# MB1296-STLINK.net
KiCad netlist of a schematic drawn in Altium Designer
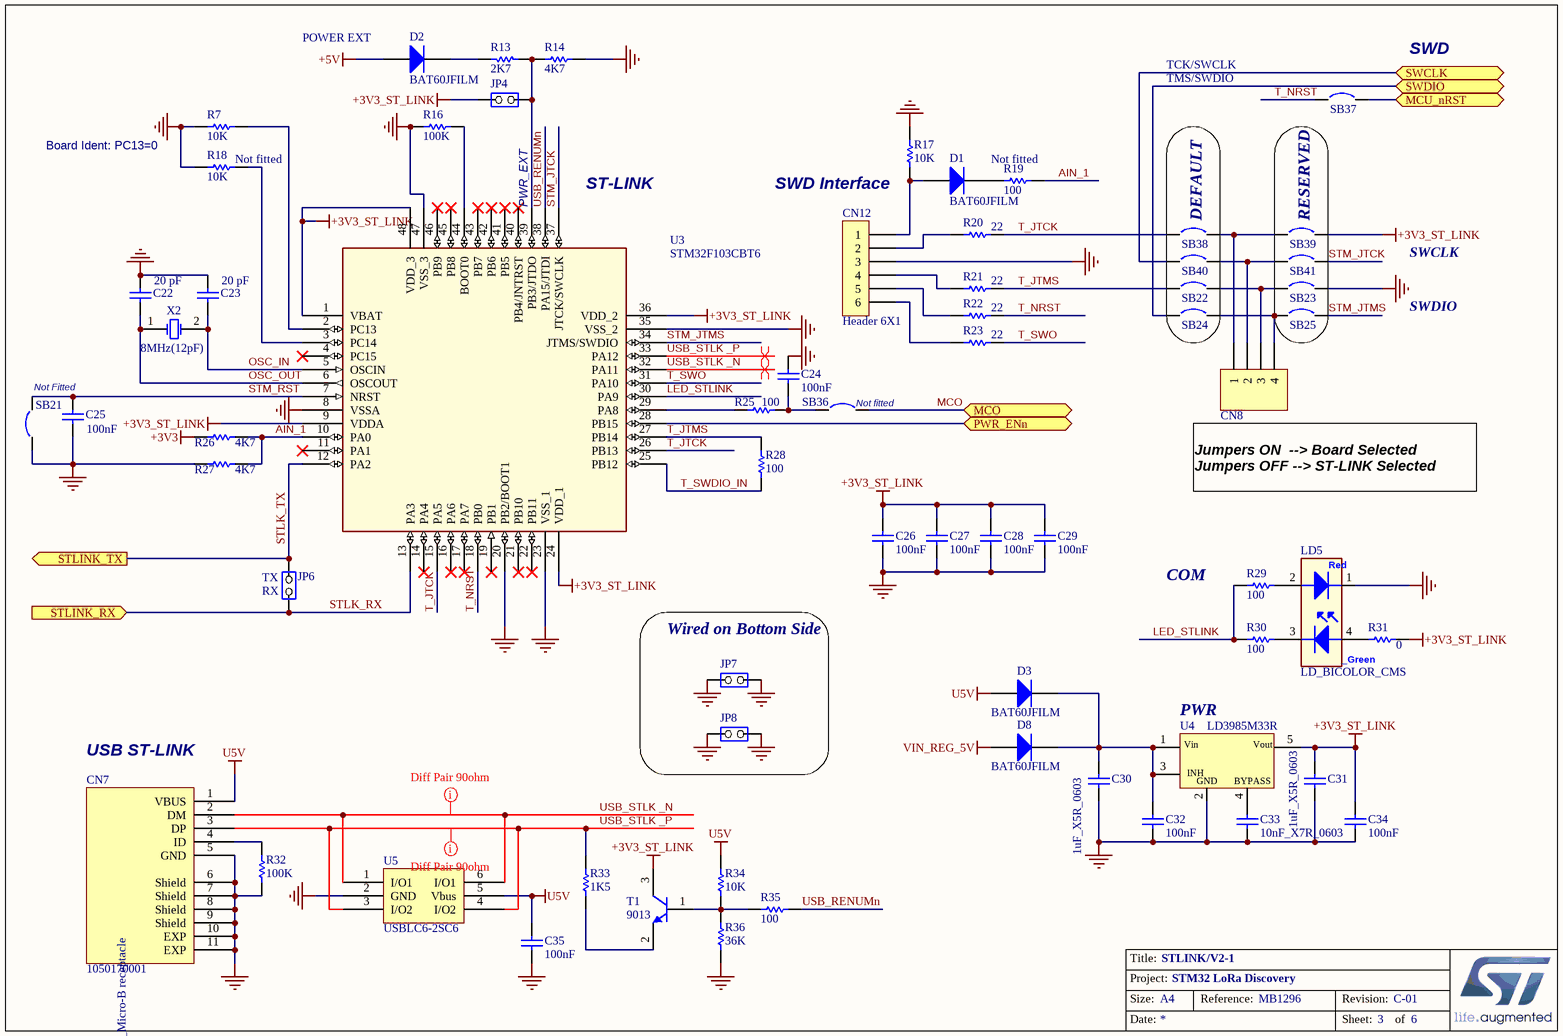
[diagram p0: MB1296-STLINK.SchDoc]

(export (version "E")
  (design (tool "Eeschema 10.0.6"))
  (components
    (comp (ref "C22")
      (value "20 pF")
      (footprint "0603C")
      (description "Capacitor 0603")
      (fields (field (name "MANUFACTURER") "YAGEO") (field (name "PROVIDED BY") "Subcon"))
      (libsource (lib "MCD16-033-STM32_LRA_Eval_Board_1") (part "Capacitor_ST"))
    )
    (comp (ref "C23")
      (value "20 pF")
      (footprint "0603C")
      (description "Capacitor 0603")
      (fields (field (name "MANUFACTURER") "YAGEO") (field (name "PROVIDED BY") "Subcon"))
      (libsource (lib "MCD16-033-STM32_LRA_Eval_Board_1") (part "Capacitor_ST"))
    )
    (comp (ref "C24")
      (value "100nF")
      (footprint "0603C")
      (description "Capacitor 100nF")
      (fields (field (name "MANUFACTURER") "YAGEO") (field (name "PROVIDED BY") "Subcon"))
      (libsource (lib "MCD16-033-STM32_LRA_Eval_Board_1") (part "CAP"))
    )
    (comp (ref "C25")
      (value "100nF")
      (footprint "0603C")
      (description "Capacitor 100nF")
      (fields (field (name "MANUFACTURER") "YAGEO") (field (name "PROVIDED BY") "Subcon"))
      (libsource (lib "MCD16-033-STM32_LRA_Eval_Board_1") (part "CAP"))
    )
    (comp (ref "C26")
      (value "100nF")
      (footprint "0603C")
      (description "Capacitor 100nF")
      (fields (field (name "MANUFACTURER") "YAGEO") (field (name "PROVIDED BY") "Subcon"))
      (libsource (lib "MCD16-033-STM32_LRA_Eval_Board_1") (part "CAP"))
    )
    (comp (ref "C27")
      (value "100nF")
      (footprint "0603C")
      (description "Capacitor 100nF")
      (fields (field (name "MANUFACTURER") "YAGEO") (field (name "PROVIDED BY") "Subcon"))
      (libsource (lib "MCD16-033-STM32_LRA_Eval_Board_1") (part "CAP"))
    )
    (comp (ref "C28")
      (value "100nF")
      (footprint "0603C")
      (description "Capacitor 100nF")
      (fields (field (name "MANUFACTURER") "YAGEO") (field (name "PROVIDED BY") "Subcon"))
      (libsource (lib "MCD16-033-STM32_LRA_Eval_Board_1") (part "CAP"))
    )
    (comp (ref "C29")
      (value "100nF")
      (footprint "0603C")
      (description "Capacitor 100nF")
      (fields (field (name "MANUFACTURER") "YAGEO") (field (name "PROVIDED BY") "Subcon"))
      (libsource (lib "MCD16-033-STM32_LRA_Eval_Board_1") (part "CAP"))
    )
    (comp (ref "C30")
      (value "1uF_X5R_0603")
      (footprint "0603C")
      (description "0603  X5R 1µF")
      (fields (field (name "MANUFACTURER") "YAGEO") (field (name "PROVIDED BY") "Subcon"))
      (libsource (lib "MCD16-033-STM32_LRA_Eval_Board_1") (part "CAP SMD 0603  X5R 1µF 25V 10%"))
    )
    (comp (ref "C31")
      (value "1uF_X5R_0603")
      (footprint "0603C")
      (description "0603  X5R 1µF")
      (fields (field (name "MANUFACTURER") "YAGEO") (field (name "PROVIDED BY") "Subcon"))
      (libsource (lib "MCD16-033-STM32_LRA_Eval_Board_1") (part "CAP SMD 0603  X5R 1µF 25V 10%"))
    )
    (comp (ref "C32")
      (value "100nF")
      (footprint "0603C")
      (description "Capacitor 100nF")
      (fields (field (name "MANUFACTURER") "YAGEO") (field (name "PROVIDED BY") "Subcon"))
      (libsource (lib "MCD16-033-STM32_LRA_Eval_Board_1") (part "CAP"))
    )
    (comp (ref "C33")
      (value "10nF_X7R_0603")
      (footprint "0603C")
      (description "0603  X7R 10NF")
      (fields (field (name "MANUFACTURER") "YAGEO") (field (name "PROVIDED BY") "Subcon"))
      (libsource (lib "MCD16-033-STM32_LRA_Eval_Board_1") (part "CAP SMD 0603  X7R 10000PF 50V 10%"))
    )
    (comp (ref "C34")
      (value "100nF")
      (footprint "0603C")
      (description "Capacitor 100nF")
      (fields (field (name "MANUFACTURER") "YAGEO") (field (name "PROVIDED BY") "Subcon"))
      (libsource (lib "MCD16-033-STM32_LRA_Eval_Board_1") (part "CAP"))
    )
    (comp (ref "C35")
      (value "100nF")
      (footprint "0603C")
      (description "Capacitor 100nF")
      (fields (field (name "MANUFACTURER") "YAGEO") (field (name "PROVIDED BY") "Subcon"))
      (libsource (lib "MCD16-033-STM32_LRA_Eval_Board_1") (part "CAP"))
    )
    (comp (ref "CN7")
      (value "1050170001")
      (footprint "Molex_1050170001")
      (libsource (lib "Smartphone_accessory") (part "1050170001"))
    )
    (comp (ref "CN8")
      (value "Header 4")
      (footprint "SIP4")
      (description "Header, 4-Pin, Single row")
      (fields (field (name "MANUFACTURER") "Lyconn") (field (name "PROVIDED BY") "Subcon"))
      (libsource (lib "MCD16-033-STM32_LRA_Eval_Board_1") (part "Header 4"))
    )
    (comp (ref "CN12")
      (value "Header 6X1")
      (footprint "Header 1x6 Female (Wrapping)")
      (description "Header, 6-Pin, Single row")
      (fields (field (name "MANUFACTURER") "Lyconn") (field (name "PROVIDED BY") "Subcon"))
      (libsource (lib "MCD16-033-STM32_LRA_Eval_Board_1") (part "Header 6X1"))
    )
    (comp (ref "D1")
      (value "BAT60JFILM")
      (footprint "SOD323/A")
      (fields (field (name "MANUFACTURER") "STM"))
      (libsource (lib "MCD16-033-STM32_LRA_Eval_Board_1") (part "BAT60JFILM"))
    )
    (comp (ref "D2")
      (value "BAT60JFILM")
      (footprint "SOD323/A")
      (fields (field (name "MANUFACTURER") "STM"))
      (libsource (lib "MCD16-033-STM32_LRA_Eval_Board_1") (part "BAT60JFILM"))
    )
    (comp (ref "D3")
      (value "BAT60JFILM")
      (footprint "SOD323/A")
      (fields (field (name "MANUFACTURER") "STM"))
      (libsource (lib "MCD16-033-STM32_LRA_Eval_Board_1") (part "BAT60JFILM"))
    )
    (comp (ref "D8")
      (value "BAT60JFILM")
      (footprint "SOD323/A")
      (fields (field (name "MANUFACTURER") "STM"))
      (libsource (lib "MCD16-033-STM32_LRA_Eval_Board_1") (part "BAT60JFILM"))
    )
    (comp (ref "JP4")
      (value "~")
      (footprint "SIP2/2.54")
      (fields (field (name "MANUFACTURER") "Lyconn") (field (name "PROVIDED BY") "Subcon"))
      (libsource (lib "MCD16-033-STM32_LRA_Eval_Board_1") (part "JP2"))
    )
    (comp (ref "JP6")
      (value "~")
      (footprint "SIP2/2.54")
      (fields (field (name "MANUFACTURER") "Lyconn") (field (name "PROVIDED BY") "Subcon"))
      (libsource (lib "MCD16-033-STM32_LRA_Eval_Board_1") (part "JP2"))
    )
    (comp (ref "JP7")
      (value "~")
      (footprint "SIP2/2.54-BOT")
      (fields (field (name "MANUFACTURER") "Lyconn") (field (name "PROVIDED BY") "Subcon"))
      (libsource (lib "MCD16-033-STM32_LRA_Eval_Board_1") (part "JP2"))
    )
    (comp (ref "JP8")
      (value "~")
      (footprint "SIP2/2.54-BOT")
      (fields (field (name "MANUFACTURER") "Lyconn") (field (name "PROVIDED BY") "Subcon"))
      (libsource (lib "MCD16-033-STM32_LRA_Eval_Board_1") (part "JP2"))
    )
    (comp (ref "LD5")
      (value "LD_BICOLOR_CMS")
      (footprint "LED SMD HSMF-A201-A00J1")
      (description "Bicolor Led")
      (fields (field (name "MANUFACTURER") "everluck-led") (field (name "PROVIDED BY") "Subcon"))
      (libsource (lib "MCD16-033-STM32_LRA_Eval_Board_1") (part "LD_BICOLOR_CMS"))
    )
    (comp (ref "R7")
      (value "10K")
      (footprint "0603")
      (description "Resistor 0603")
      (fields (field (name "MANUFACTURER") "YAGEO") (field (name "PROVIDED BY") "Subcon"))
      (libsource (lib "MCD16-033-STM32_LRA_Eval_Board_1") (part "Resistor_ST"))
    )
    (comp (ref "R13")
      (value "2K7")
      (description "Resistor")
      (fields (field (name "PUBLISHER") "Altium Limited"))
      (libsource (lib "") (part "Res1_2"))
    )
    (comp (ref "R14")
      (value "4K7")
      (description "Resistor")
      (fields (field (name "MANUFACTURER") "YAGEO") (field (name "PROVIDED BY") "Subcon"))
      (libsource (lib "MCD16-033-STM32_LRA_Eval_Board_1") (part "res1_4"))
    )
    (comp (ref "R16")
      (value "100K")
      (footprint "0603")
      (description "0603 100K 75V 5% 0.1W")
      (fields (field (name "MANUFACTURER") "YAGEO") (field (name "PROVIDED BY") "Subcon"))
      (libsource (lib "MCD16-033-STM32_LRA_Eval_Board_1") (part "RES SMD 0603 100K 75V 5% 0.1W"))
    )
    (comp (ref "R17")
      (value "10K")
      (footprint "0603")
      (description "Resistor 0603")
      (fields (field (name "MANUFACTURER") "YAGEO") (field (name "PROVIDED BY") "Subcon"))
      (libsource (lib "MCD16-033-STM32_LRA_Eval_Board_1") (part "Resistor_ST"))
    )
    (comp (ref "R18")
      (value "10K")
      (footprint "0603")
      (description "Resistor 0603")
      (fields (field (name "MANUFACTURER") "YAGEO") (field (name "PROVIDED BY") "Subcon"))
      (libsource (lib "MCD16-033-STM32_LRA_Eval_Board_1") (part "Resistor_ST"))
    )
    (comp (ref "R19")
      (value "100")
      (footprint "0603")
      (description "Resistor 0603")
      (fields (field (name "MANUFACTURER") "YAGEO") (field (name "PROVIDED BY") "Subcon"))
      (libsource (lib "MCD16-033-STM32_LRA_Eval_Board_1") (part "Res1_1"))
    )
    (comp (ref "R20")
      (value "22")
      (footprint "0603")
      (description "Resistor 0603")
      (fields (field (name "MANUFACTURER") "YAGEO") (field (name "PROVIDED BY") "Subcon"))
      (libsource (lib "MCD16-033-STM32_LRA_Eval_Board_1") (part "Res1_1"))
    )
    (comp (ref "R21")
      (value "22")
      (footprint "0603")
      (description "Resistor 0603")
      (fields (field (name "MANUFACTURER") "YAGEO") (field (name "PROVIDED BY") "Subcon"))
      (libsource (lib "MCD16-033-STM32_LRA_Eval_Board_1") (part "Res1_1"))
    )
    (comp (ref "R22")
      (value "22")
      (footprint "0603")
      (description "Resistor 0603")
      (fields (field (name "MANUFACTURER") "YAGEO") (field (name "PROVIDED BY") "Subcon"))
      (libsource (lib "MCD16-033-STM32_LRA_Eval_Board_1") (part "Res1_1"))
    )
    (comp (ref "R23")
      (value "22")
      (footprint "0603")
      (description "Resistor 0603")
      (fields (field (name "MANUFACTURER") "YAGEO") (field (name "PROVIDED BY") "Subcon"))
      (libsource (lib "MCD16-033-STM32_LRA_Eval_Board_1") (part "Res1_1"))
    )
    (comp (ref "R25")
      (value "100")
      (footprint "0603")
      (description "Resistor 0603")
      (fields (field (name "MANUFACTURER") "YAGEO") (field (name "PROVIDED BY") "Subcon"))
      (libsource (lib "MCD16-033-STM32_LRA_Eval_Board_1") (part "Res1_1"))
    )
    (comp (ref "R26")
      (value "4K7")
      (description "Resistor")
      (fields (field (name "MANUFACTURER") "YAGEO") (field (name "PROVIDED BY") "Subcon"))
      (libsource (lib "MCD16-033-STM32_LRA_Eval_Board_1") (part "res1_4"))
    )
    (comp (ref "R27")
      (value "4K7")
      (description "Resistor")
      (fields (field (name "MANUFACTURER") "YAGEO") (field (name "PROVIDED BY") "Subcon"))
      (libsource (lib "MCD16-033-STM32_LRA_Eval_Board_1") (part "res1_4"))
    )
    (comp (ref "R28")
      (value "100")
      (footprint "0603")
      (description "Resistor 0603")
      (fields (field (name "MANUFACTURER") "YAGEO") (field (name "PROVIDED BY") "Subcon"))
      (libsource (lib "MCD16-033-STM32_LRA_Eval_Board_1") (part "Res1_1"))
    )
    (comp (ref "R29")
      (value "100")
      (footprint "0603")
      (description "Resistor 0603")
      (fields (field (name "MANUFACTURER") "YAGEO") (field (name "PROVIDED BY") "Subcon"))
      (libsource (lib "MCD16-033-STM32_LRA_Eval_Board_1") (part "Res1_1"))
    )
    (comp (ref "R30")
      (value "100")
      (footprint "0603")
      (description "Resistor 0603")
      (fields (field (name "MANUFACTURER") "YAGEO") (field (name "PROVIDED BY") "Subcon"))
      (libsource (lib "MCD16-033-STM32_LRA_Eval_Board_1") (part "Res1_1"))
    )
    (comp (ref "R31")
      (value "0")
      (footprint "0603")
      (description "Resistor 0402 / 0603 / 0805")
      (libsource (lib "") (part "Res1_1"))
    )
    (comp (ref "R32")
      (value "100K")
      (footprint "0603")
      (description "0603 100K 75V 5% 0.1W")
      (fields (field (name "MANUFACTURER") "YAGEO") (field (name "PROVIDED BY") "Subcon"))
      (libsource (lib "MCD16-033-STM32_LRA_Eval_Board_1") (part "RES SMD 0603 100K 75V 5% 0.1W"))
    )
    (comp (ref "R33")
      (value "1K5")
      (footprint "0603")
      (description "0603 1K5 75V 5% 0.1W")
      (fields (field (name "MANUFACTURER") "YAGEO") (field (name "PROVIDED BY") "Subcon"))
      (libsource (lib "MCD16-033-STM32_LRA_Eval_Board_1") (part "RES SMD 0603 100K 75V 5% 0.1W"))
    )
    (comp (ref "R34")
      (value "10K")
      (footprint "0603")
      (description "Resistor 0603")
      (fields (field (name "MANUFACTURER") "YAGEO") (field (name "PROVIDED BY") "Subcon"))
      (libsource (lib "MCD16-033-STM32_LRA_Eval_Board_1") (part "Resistor_ST"))
    )
    (comp (ref "R35")
      (value "100")
      (footprint "0603")
      (description "Resistor 0603")
      (fields (field (name "MANUFACTURER") "YAGEO") (field (name "PROVIDED BY") "Subcon"))
      (libsource (lib "MCD16-033-STM32_LRA_Eval_Board_1") (part "Res1_1"))
    )
    (comp (ref "R36")
      (value "36K")
      (description "Resistor")
      (fields (field (name "PUBLISHER") "Altium Limited"))
      (libsource (lib "Miscellaneous Devices") (part "Res1"))
    )
    (comp (ref "SB21")
      (value "Circuit Breaker")
      (footprint "JP2_SMD")
      (libsource (lib "MCD16-033-STM32_LRA_Eval_Board_1") (part "Circuit Breaker"))
    )
    (comp (ref "SB22")
      (value "Circuit Breaker")
      (footprint "JP2_SMD")
      (libsource (lib "MCD16-033-STM32_LRA_Eval_Board_1") (part "Circuit Breaker"))
    )
    (comp (ref "SB23")
      (value "Circuit Breaker")
      (footprint "SB-tiny")
      (libsource (lib "MCD16-033-STM32_LRA_Eval_Board_1") (part "Circuit Breaker"))
    )
    (comp (ref "SB24")
      (value "Circuit Breaker")
      (footprint "JP2_SMD")
      (libsource (lib "MCD16-033-STM32_LRA_Eval_Board_1") (part "Circuit Breaker"))
    )
    (comp (ref "SB25")
      (value "Circuit Breaker")
      (footprint "SB-tiny")
      (libsource (lib "MCD16-033-STM32_LRA_Eval_Board_1") (part "Circuit Breaker"))
    )
    (comp (ref "SB36")
      (value "Circuit Breaker")
      (footprint "JP2_SMD")
      (libsource (lib "MCD16-033-STM32_LRA_Eval_Board_1") (part "Circuit Breaker"))
    )
    (comp (ref "SB37")
      (value "Circuit Breaker")
      (footprint "JP2_SMD")
      (libsource (lib "MCD16-033-STM32_LRA_Eval_Board_1") (part "Circuit Breaker"))
    )
    (comp (ref "SB38")
      (value "Circuit Breaker")
      (footprint "JP2_SMD")
      (libsource (lib "MCD16-033-STM32_LRA_Eval_Board_1") (part "Circuit Breaker"))
    )
    (comp (ref "SB39")
      (value "Circuit Breaker")
      (footprint "SB-tiny")
      (libsource (lib "MCD16-033-STM32_LRA_Eval_Board_1") (part "Circuit Breaker"))
    )
    (comp (ref "SB40")
      (value "Circuit Breaker")
      (footprint "JP2_SMD")
      (libsource (lib "MCD16-033-STM32_LRA_Eval_Board_1") (part "Circuit Breaker"))
    )
    (comp (ref "SB41")
      (value "Circuit Breaker")
      (footprint "SB-tiny")
      (libsource (lib "MCD16-033-STM32_LRA_Eval_Board_1") (part "Circuit Breaker"))
    )
    (comp (ref "T1")
      (value "9013")
      (footprint "SOT-23")
      (description "NPN Bipolar Transistor")
      (fields (field (name "MANUFACTURER") "STMicroelectronics") (field (name "PROVIDED BY") "STM"))
      (libsource (lib "MB1167") (part "NPN"))
    )
    (comp (ref "U3")
      (value "STM32F103CBT6")
      (footprint "QFP48 7X7")
      (description "Medium-density performance line ARM-based 32-bit MCU with 64KB Flash")
      (fields (field (name "MANUFACTURER") "STM"))
      (libsource (lib "Nucleo_64") (part "STM32F103CBT6"))
    )
    (comp (ref "U4")
      (value "LD3985M33R")
      (footprint "SOT-23-5L")
      (description "Ultra low drop-low noise BiCMOS voltage, regulators low ESR capacitors compatible")
      (fields (field (name "MANUFACTURER") "STM") (field (name "PROVIDED BY") "STM"))
      (libsource (lib "MCD16-033-STM32_LRA_Eval_Board_1") (part "LD3985M33R"))
    )
    (comp (ref "U5")
      (value "USBLC6-2SC6")
      (footprint "SOT23-6L")
      (fields (field (name "MANUFACTURER") "STMicroelectronics") (field (name "PROVIDED BY") "STM"))
      (libsource (lib "MB1137") (part "USBLC6-2SC6"))
    )
    (comp (ref "X2")
      (value "8MHz(12pF)")
      (footprint "CRY_NX3225GD_2P")
      (description "Crystal Oscillator")
      (fields (field (name "MANUFACTURER") "HongKongCrystal") (field (name "PROVIDED BY") "Subcon"))
      (libsource (lib "MB963_1") (part "XTAL"))
    )
  )
  (nets
    (net (code "1") (name "+3V3") (class "Default")
      (node (ref "R26") (pin "1") (pinfunction "1_1") (pintype "passive"))
    )
    (net (code "2") (name "+3V3_ST_LINK") (class "Default")
      (node (ref "C26") (pin "2") (pinfunction "2_2") (pintype "passive"))
      (node (ref "C27") (pin "2") (pinfunction "2_2") (pintype "passive"))
      (node (ref "C28") (pin "2") (pinfunction "2_2") (pintype "passive"))
      (node (ref "C29") (pin "2") (pinfunction "2_2") (pintype "passive"))
      (node (ref "C31") (pin "2") (pinfunction "2_2") (pintype "passive"))
      (node (ref "C34") (pin "2") (pinfunction "2_2") (pintype "passive"))
      (node (ref "JP4") (pin "1") (pinfunction "COMMON_1") (pintype "passive"))
      (node (ref "R31") (pin "2") (pinfunction "2_2") (pintype "passive"))
      (node (ref "SB39") (pin "2") (pinfunction "2_2") (pintype "passive"))
      (node (ref "T1") (pin "3") (pinfunction "C_3") (pintype "passive"))
      (node (ref "U3") (pin "1") (pinfunction "VBAT_1") (pintype "power_in"))
      (node (ref "U3") (pin "24") (pinfunction "VDD_1_24") (pintype "power_in"))
      (node (ref "U3") (pin "36") (pinfunction "VDD_2_36") (pintype "power_in"))
      (node (ref "U3") (pin "48") (pinfunction "VDD_3_48") (pintype "power_in"))
      (node (ref "U3") (pin "9") (pinfunction "VDDA_9") (pintype "power_in"))
      (node (ref "U4") (pin "5") (pinfunction "Vout_5") (pintype "passive"))
    )
    (net (code "3") (name "+5V") (class "Default")
      (node (ref "D2") (pin "1") (pinfunction "A_1") (pintype "passive"))
    )
    (net (code "4") (name "/AIN_1") (class "Default")
      (node (ref "R19") (pin "1") (pinfunction "1_1") (pintype "passive"))
      (node (ref "R26") (pin "2") (pinfunction "2_2") (pintype "passive"))
      (node (ref "R27") (pin "2") (pinfunction "2_2") (pintype "passive"))
      (node (ref "U3") (pin "10") (pinfunction "PA0_10") (pintype "bidirectional"))
    )
    (net (code "5") (name "/LED_STLINK") (class "Default")
      (node (ref "R29") (pin "2") (pinfunction "2_2") (pintype "passive"))
      (node (ref "R30") (pin "2") (pinfunction "2_2") (pintype "passive"))
      (node (ref "U3") (pin "30") (pinfunction "PA9_30") (pintype "bidirectional"))
    )
    (net (code "6") (name "/MCO") (class "Default")
      (node (ref "SB36") (pin "2") (pinfunction "2_2") (pintype "passive"))
    )
    (net (code "7") (name "/MCU_nRST") (class "Default")
      (node (ref "SB37") (pin "2") (pinfunction "2_2") (pintype "passive"))
    )
    (net (code "8") (name "/OSC_IN") (class "Default")
      (node (ref "C23") (pin "1") (pinfunction "1_1") (pintype "passive"))
      (node (ref "U3") (pin "5") (pinfunction "OSCIN_5") (pintype "input"))
      (node (ref "X2") (pin "2") (pinfunction "OSC2_2") (pintype "passive"))
    )
    (net (code "9") (name "/OSC_OUT") (class "Default")
      (node (ref "C22") (pin "1") (pinfunction "1_1") (pintype "passive"))
      (node (ref "U3") (pin "6") (pinfunction "OSCOUT_6") (pintype "output"))
      (node (ref "X2") (pin "1") (pinfunction "OSC1_1") (pintype "passive"))
    )
    (net (code "10") (name "/PWR_ENn") (class "Default")
      (node (ref "U3") (pin "28") (pinfunction "PB15_28") (pintype "bidirectional"))
    )
    (net (code "11") (name "/STLK_RX") (class "Default")
      (node (ref "JP6") (pin "1") (pinfunction "COMMON_1") (pintype "passive"))
      (node (ref "U3") (pin "13") (pinfunction "PA3_13") (pintype "bidirectional"))
    )
    (net (code "12") (name "/STLK_TX") (class "Default")
      (node (ref "JP6") (pin "2") (pinfunction "NO_2") (pintype "passive"))
      (node (ref "U3") (pin "12") (pinfunction "PA2_12") (pintype "bidirectional"))
    )
    (net (code "13") (name "/STM_JTCK") (class "Default")
      (node (ref "SB41") (pin "2") (pinfunction "2_2") (pintype "passive"))
      (node (ref "U3") (pin "37") (pinfunction "JTCK/SWCLK_37") (pintype "bidirectional"))
    )
    (net (code "14") (name "/STM_JTMS") (class "Default")
      (node (ref "SB25") (pin "2") (pinfunction "2_2") (pintype "passive"))
      (node (ref "U3") (pin "34") (pinfunction "JTMS/SWDIO_34") (pintype "bidirectional"))
    )
    (net (code "15") (name "/STM_RST") (class "Default")
      (node (ref "C25") (pin "2") (pinfunction "2_2") (pintype "passive"))
      (node (ref "SB21") (pin "2") (pinfunction "2_2") (pintype "passive"))
      (node (ref "U3") (pin "7") (pinfunction "NRST_7") (pintype "input"))
    )
    (net (code "16") (name "/SWCLK") (class "Default")
      (node (ref "SB40") (pin "1") (pinfunction "1_1") (pintype "passive"))
    )
    (net (code "17") (name "/SWDIO") (class "Default")
      (node (ref "SB24") (pin "1") (pinfunction "1_1") (pintype "passive"))
    )
    (net (code "18") (name "/T_JTCK") (class "Default")
      (node (ref "R20") (pin "1") (pinfunction "1_1") (pintype "passive"))
      (node (ref "SB38") (pin "1") (pinfunction "1_1") (pintype "passive"))
      (node (ref "U3") (pin "15") (pinfunction "PA5_15") (pintype "bidirectional"))
      (node (ref "U3") (pin "26") (pinfunction "PB13_26") (pintype "bidirectional"))
    )
    (net (code "19") (name "/T_JTMS") (class "Default")
      (node (ref "R21") (pin "1") (pinfunction "1_1") (pintype "passive"))
      (node (ref "R28") (pin "2") (pinfunction "2_2") (pintype "passive"))
      (node (ref "SB22") (pin "1") (pinfunction "1_1") (pintype "passive"))
      (node (ref "U3") (pin "27") (pinfunction "PB14_27") (pintype "bidirectional"))
    )
    (net (code "20") (name "/T_NRST") (class "Default")
      (node (ref "R22") (pin "1") (pinfunction "1_1") (pintype "passive"))
      (node (ref "SB37") (pin "1") (pinfunction "1_1") (pintype "passive"))
      (node (ref "U3") (pin "18") (pinfunction "PB0_18") (pintype "bidirectional"))
    )
    (net (code "21") (name "/T_SWDIO_IN") (class "Default")
      (node (ref "R28") (pin "1") (pinfunction "1_1") (pintype "passive"))
      (node (ref "U3") (pin "25") (pinfunction "PB12_25") (pintype "bidirectional"))
    )
    (net (code "22") (name "/T_SWO") (class "Default")
      (node (ref "R23") (pin "1") (pinfunction "1_1") (pintype "passive"))
      (node (ref "U3") (pin "31") (pinfunction "PA10_31") (pintype "bidirectional"))
    )
    (net (code "23") (name "/USB_RENUMn") (class "Default")
      (node (ref "R35") (pin "1") (pinfunction "1_1") (pintype "passive"))
      (node (ref "U3") (pin "38") (pinfunction "PA15/JTDI_38") (pintype "bidirectional"))
    )
    (net (code "24") (name "/USB_STLK _N") (class "Default")
      (node (ref "CN7") (pin "2") (pinfunction "DM_2") (pintype "passive"))
      (node (ref "U3") (pin "32") (pinfunction "PA11_32") (pintype "bidirectional"))
      (node (ref "U5") (pin "1") (pinfunction "I/O1_1") (pintype "passive"))
      (node (ref "U5") (pin "6") (pinfunction "I/O1_6") (pintype "passive"))
    )
    (net (code "25") (name "/USB_STLK _P") (class "Default")
      (node (ref "CN7") (pin "3") (pinfunction "DP_3") (pintype "passive"))
      (node (ref "R33") (pin "2") (pinfunction "2_2") (pintype "passive"))
      (node (ref "U3") (pin "33") (pinfunction "PA12_33") (pintype "bidirectional"))
      (node (ref "U5") (pin "3") (pinfunction "I/O2_3") (pintype "passive"))
      (node (ref "U5") (pin "4") (pinfunction "I/O2_4") (pintype "passive"))
    )
    (net (code "26") (name "GND") (class "Default")
      (node (ref "C22") (pin "2") (pinfunction "2_2") (pintype "passive"))
      (node (ref "C23") (pin "2") (pinfunction "2_2") (pintype "passive"))
      (node (ref "C24") (pin "2") (pinfunction "2_2") (pintype "passive"))
      (node (ref "C25") (pin "1") (pinfunction "1_1") (pintype "passive"))
      (node (ref "C26") (pin "1") (pinfunction "1_1") (pintype "passive"))
      (node (ref "C27") (pin "1") (pinfunction "1_1") (pintype "passive"))
      (node (ref "C28") (pin "1") (pinfunction "1_1") (pintype "passive"))
      (node (ref "C29") (pin "1") (pinfunction "1_1") (pintype "passive"))
      (node (ref "C30") (pin "1") (pinfunction "1_1") (pintype "passive"))
      (node (ref "C31") (pin "1") (pinfunction "1_1") (pintype "passive"))
      (node (ref "C32") (pin "1") (pinfunction "1_1") (pintype "passive"))
      (node (ref "C33") (pin "1") (pinfunction "1_1") (pintype "passive"))
      (node (ref "C34") (pin "1") (pinfunction "1_1") (pintype "passive"))
      (node (ref "C35") (pin "1") (pinfunction "1_1") (pintype "passive"))
      (node (ref "CN12") (pin "3") (pinfunction "3_3") (pintype "passive"))
      (node (ref "CN7") (pin "10") (pinfunction "EXP_10") (pintype "passive"))
      (node (ref "CN7") (pin "11") (pinfunction "EXP_11") (pintype "passive"))
      (node (ref "CN7") (pin "5") (pinfunction "GND_5") (pintype "passive"))
      (node (ref "CN7") (pin "6") (pinfunction "Shield_6") (pintype "passive"))
      (node (ref "CN7") (pin "7") (pinfunction "Shield_7") (pintype "passive"))
      (node (ref "CN7") (pin "8") (pinfunction "Shield_8") (pintype "passive"))
      (node (ref "CN7") (pin "9") (pinfunction "Shield_9") (pintype "passive"))
      (node (ref "JP7") (pin "1") (pinfunction "COMMON_1") (pintype "passive"))
      (node (ref "JP7") (pin "2") (pinfunction "NO_2") (pintype "passive"))
      (node (ref "JP8") (pin "1") (pinfunction "COMMON_1") (pintype "passive"))
      (node (ref "JP8") (pin "2") (pinfunction "NO_2") (pintype "passive"))
      (node (ref "LD5") (pin "1") (pinfunction "1_1") (pintype "passive"))
      (node (ref "R14") (pin "2") (pinfunction "2_2") (pintype "passive"))
      (node (ref "R16") (pin "2") (pinfunction "2_2") (pintype "passive"))
      (node (ref "R17") (pin "1") (pinfunction "1_1") (pintype "passive"))
      (node (ref "R18") (pin "2") (pinfunction "2_2") (pintype "passive"))
      (node (ref "R27") (pin "1") (pinfunction "1_1") (pintype "passive"))
      (node (ref "R32") (pin "1") (pinfunction "1_1") (pintype "passive"))
      (node (ref "R36") (pin "1") (pinfunction "1_1") (pintype "passive"))
      (node (ref "R7") (pin "2") (pinfunction "2_2") (pintype "passive"))
      (node (ref "SB21") (pin "1") (pinfunction "1_1") (pintype "passive"))
      (node (ref "SB23") (pin "2") (pinfunction "2_2") (pintype "passive"))
      (node (ref "U3") (pin "20") (pinfunction "PB2/BOOT1_20") (pintype "bidirectional"))
      (node (ref "U3") (pin "23") (pinfunction "VSS_1_23") (pintype "power_in"))
      (node (ref "U3") (pin "35") (pinfunction "VSS_2_35") (pintype "power_in"))
      (node (ref "U3") (pin "47") (pinfunction "VSS_3_47") (pintype "power_in"))
      (node (ref "U3") (pin "8") (pinfunction "VSSA_8") (pintype "power_in"))
      (node (ref "U4") (pin "2") (pinfunction "GND_2") (pintype "passive"))
      (node (ref "U5") (pin "2") (pinfunction "GND_2") (pintype "passive"))
    )
    (net (code "27") (name "Net-(C24-Pad1)") (class "Default")
      (node (ref "C24") (pin "1") (pinfunction "1_1") (pintype "passive"))
      (node (ref "R25") (pin "1") (pinfunction "1_1") (pintype "passive"))
      (node (ref "SB36") (pin "1") (pinfunction "1_1") (pintype "passive"))
    )
    (net (code "28") (name "Net-(CN7-ID)") (class "Default")
      (node (ref "CN7") (pin "4") (pinfunction "ID_4") (pintype "passive"))
      (node (ref "R32") (pin "2") (pinfunction "2_2") (pintype "passive"))
    )
    (net (code "29") (name "Net-(CN8-Pad1)") (class "Default")
      (node (ref "CN8") (pin "1") (pinfunction "1_1") (pintype "passive"))
      (node (ref "SB38") (pin "2") (pinfunction "2_2") (pintype "passive"))
      (node (ref "SB39") (pin "1") (pinfunction "1_1") (pintype "passive"))
    )
    (net (code "30") (name "Net-(CN8-Pad2)") (class "Default")
      (node (ref "CN8") (pin "2") (pinfunction "2_2") (pintype "passive"))
      (node (ref "SB40") (pin "2") (pinfunction "2_2") (pintype "passive"))
      (node (ref "SB41") (pin "1") (pinfunction "1_1") (pintype "passive"))
    )
    (net (code "31") (name "Net-(CN8-Pad3)") (class "Default")
      (node (ref "CN8") (pin "3") (pinfunction "3_3") (pintype "passive"))
      (node (ref "SB22") (pin "2") (pinfunction "2_2") (pintype "passive"))
      (node (ref "SB23") (pin "1") (pinfunction "1_1") (pintype "passive"))
    )
    (net (code "32") (name "Net-(CN8-Pad4)") (class "Default")
      (node (ref "CN8") (pin "4") (pinfunction "4_4") (pintype "passive"))
      (node (ref "SB24") (pin "2") (pinfunction "2_2") (pintype "passive"))
      (node (ref "SB25") (pin "1") (pinfunction "1_1") (pintype "passive"))
    )
    (net (code "33") (name "Net-(CN12-Pad2)") (class "Default")
      (node (ref "CN12") (pin "2") (pinfunction "2_2") (pintype "passive"))
      (node (ref "R20") (pin "2") (pinfunction "2_2") (pintype "passive"))
    )
    (net (code "34") (name "Net-(CN12-Pad4)") (class "Default")
      (node (ref "CN12") (pin "4") (pinfunction "4_4") (pintype "passive"))
      (node (ref "R21") (pin "2") (pinfunction "2_2") (pintype "passive"))
    )
    (net (code "35") (name "Net-(CN12-Pad5)") (class "Default")
      (node (ref "CN12") (pin "5") (pinfunction "5_5") (pintype "passive"))
      (node (ref "R22") (pin "2") (pinfunction "2_2") (pintype "passive"))
    )
    (net (code "36") (name "Net-(CN12-Pad6)") (class "Default")
      (node (ref "CN12") (pin "6") (pinfunction "6_6") (pintype "passive"))
      (node (ref "R23") (pin "2") (pinfunction "2_2") (pintype "passive"))
    )
    (net (code "37") (name "Net-(D1-A)") (class "Default")
      (node (ref "CN12") (pin "1") (pinfunction "1_1") (pintype "passive"))
      (node (ref "D1") (pin "1") (pinfunction "A_1") (pintype "passive"))
      (node (ref "R17") (pin "2") (pinfunction "2_2") (pintype "passive"))
    )
    (net (code "38") (name "Net-(D1-K)") (class "Default")
      (node (ref "D1") (pin "2") (pinfunction "K_2") (pintype "passive"))
      (node (ref "R19") (pin "2") (pinfunction "2_2") (pintype "passive"))
    )
    (net (code "39") (name "Net-(D2-K)") (class "Default")
      (node (ref "D2") (pin "2") (pinfunction "K_2") (pintype "passive"))
      (node (ref "R13") (pin "1") (pinfunction "1_1") (pintype "passive"))
    )
    (net (code "40") (name "Net-(D3-K)") (class "Default")
      (node (ref "C30") (pin "2") (pinfunction "2_2") (pintype "passive"))
      (node (ref "C32") (pin "2") (pinfunction "2_2") (pintype "passive"))
      (node (ref "D3") (pin "2") (pinfunction "K_2") (pintype "passive"))
      (node (ref "D8") (pin "2") (pinfunction "K_2") (pintype "passive"))
      (node (ref "U4") (pin "1") (pinfunction "Vin_1") (pintype "passive"))
      (node (ref "U4") (pin "3") (pinfunction "CE_3") (pintype "passive"))
    )
    (net (code "41") (name "Net-(JP4-NO)") (class "Default")
      (node (ref "JP4") (pin "2") (pinfunction "NO_2") (pintype "passive"))
      (node (ref "R13") (pin "2") (pinfunction "2_2") (pintype "passive"))
      (node (ref "R14") (pin "1") (pinfunction "1_1") (pintype "passive"))
      (node (ref "U3") (pin "39") (pinfunction "PB3/JTDO_39") (pintype "bidirectional"))
    )
    (net (code "42") (name "Net-(LD5-Pad2)") (class "Default")
      (node (ref "LD5") (pin "2") (pinfunction "2_2") (pintype "passive"))
      (node (ref "R29") (pin "1") (pinfunction "1_1") (pintype "passive"))
    )
    (net (code "43") (name "Net-(LD5-Pad3)") (class "Default")
      (node (ref "LD5") (pin "3") (pinfunction "3_3") (pintype "passive"))
      (node (ref "R30") (pin "1") (pinfunction "1_1") (pintype "passive"))
    )
    (net (code "44") (name "Net-(LD5-Pad4)") (class "Default")
      (node (ref "LD5") (pin "4") (pinfunction "4_4") (pintype "passive"))
      (node (ref "R31") (pin "1") (pinfunction "1_1") (pintype "passive"))
    )
    (net (code "45") (name "Net-(T1-B)") (class "Default")
      (node (ref "R34") (pin "2") (pinfunction "2_2") (pintype "passive"))
      (node (ref "R35") (pin "2") (pinfunction "2_2") (pintype "passive"))
      (node (ref "R36") (pin "2") (pinfunction "2_2") (pintype "passive"))
      (node (ref "T1") (pin "1") (pinfunction "B_1") (pintype "passive"))
    )
    (net (code "46") (name "Net-(T1-E)") (class "Default")
      (node (ref "R33") (pin "1") (pinfunction "1_1") (pintype "passive"))
      (node (ref "T1") (pin "2") (pinfunction "E_2") (pintype "passive"))
    )
    (net (code "47") (name "Net-(U3-BOOT0)") (class "Default")
      (node (ref "R16") (pin "1") (pinfunction "1_1") (pintype "passive"))
      (node (ref "U3") (pin "44") (pinfunction "BOOT0_44") (pintype "bidirectional"))
    )
    (net (code "48") (name "Net-(U3-PA8)") (class "Default")
      (node (ref "R25") (pin "2") (pinfunction "2_2") (pintype "passive"))
      (node (ref "U3") (pin "29") (pinfunction "PA8_29") (pintype "bidirectional"))
    )
    (net (code "49") (name "Net-(U3-PC13)") (class "Default")
      (node (ref "R7") (pin "1") (pinfunction "1_1") (pintype "passive"))
      (node (ref "U3") (pin "2") (pinfunction "PC13_2") (pintype "bidirectional"))
    )
    (net (code "50") (name "Net-(U3-PC14)") (class "Default")
      (node (ref "R18") (pin "1") (pinfunction "1_1") (pintype "passive"))
      (node (ref "U3") (pin "3") (pinfunction "PC14_3") (pintype "bidirectional"))
    )
    (net (code "51") (name "Net-(U4-BYPASS)") (class "Default")
      (node (ref "C33") (pin "2") (pinfunction "2_2") (pintype "passive"))
      (node (ref "U4") (pin "4") (pinfunction "BYPASS_4") (pintype "passive"))
    )
    (net (code "52") (name "U5V") (class "Default")
      (node (ref "C35") (pin "2") (pinfunction "2_2") (pintype "passive"))
      (node (ref "CN7") (pin "1") (pinfunction "VBUS_1") (pintype "passive"))
      (node (ref "D3") (pin "1") (pinfunction "A_1") (pintype "passive"))
      (node (ref "R34") (pin "1") (pinfunction "1_1") (pintype "passive"))
      (node (ref "U5") (pin "5") (pinfunction "Vbus_5") (pintype "passive"))
    )
    (net (code "53") (name "VIN_REG_5V") (class "Default")
      (node (ref "D8") (pin "1") (pinfunction "A_1") (pintype "passive"))
    )
    (net (code "54") (name "unconnected-(U3-PA1-Pad11)") (class "Default")
      (node (ref "U3") (pin "11") (pinfunction "PA1_11") (pintype "bidirectional+no_connect"))
    )
    (net (code "55") (name "unconnected-(U3-PA4-Pad14)") (class "Default")
      (node (ref "U3") (pin "14") (pinfunction "PA4_14") (pintype "bidirectional+no_connect"))
    )
    (net (code "56") (name "unconnected-(U3-PA6-Pad16)") (class "Default")
      (node (ref "U3") (pin "16") (pinfunction "PA6_16") (pintype "bidirectional+no_connect"))
    )
    (net (code "57") (name "unconnected-(U3-PA7-Pad17)") (class "Default")
      (node (ref "U3") (pin "17") (pinfunction "PA7_17") (pintype "bidirectional+no_connect"))
    )
    (net (code "58") (name "unconnected-(U3-PB1-Pad19)") (class "Default")
      (node (ref "U3") (pin "19") (pinfunction "PB1_19") (pintype "input+no_connect"))
    )
    (net (code "59") (name "unconnected-(U3-PB4{slash}JNTRST-Pad40)") (class "Default")
      (node (ref "U3") (pin "40") (pinfunction "PB4/JNTRST_40") (pintype "bidirectional+no_connect"))
    )
    (net (code "60") (name "unconnected-(U3-PB5-Pad41)") (class "Default")
      (node (ref "U3") (pin "41") (pinfunction "PB5_41") (pintype "bidirectional+no_connect"))
    )
    (net (code "61") (name "unconnected-(U3-PB6-Pad42)") (class "Default")
      (node (ref "U3") (pin "42") (pinfunction "PB6_42") (pintype "bidirectional+no_connect"))
    )
    (net (code "62") (name "unconnected-(U3-PB7-Pad43)") (class "Default")
      (node (ref "U3") (pin "43") (pinfunction "PB7_43") (pintype "bidirectional+no_connect"))
    )
    (net (code "63") (name "unconnected-(U3-PB8-Pad45)") (class "Default")
      (node (ref "U3") (pin "45") (pinfunction "PB8_45") (pintype "bidirectional+no_connect"))
    )
    (net (code "64") (name "unconnected-(U3-PB9-Pad46)") (class "Default")
      (node (ref "U3") (pin "46") (pinfunction "PB9_46") (pintype "bidirectional+no_connect"))
    )
    (net (code "65") (name "unconnected-(U3-PB10-Pad21)") (class "Default")
      (node (ref "U3") (pin "21") (pinfunction "PB10_21") (pintype "bidirectional+no_connect"))
    )
    (net (code "66") (name "unconnected-(U3-PB11-Pad22)") (class "Default")
      (node (ref "U3") (pin "22") (pinfunction "PB11_22") (pintype "bidirectional+no_connect"))
    )
    (net (code "67") (name "unconnected-(U3-PC15-Pad4)") (class "Default")
      (node (ref "U3") (pin "4") (pinfunction "PC15_4") (pintype "bidirectional+no_connect"))
    )
  )
)
